# ESP32Break_Schem.net
KiCad netlist of a schematic drawn in Altium Designer
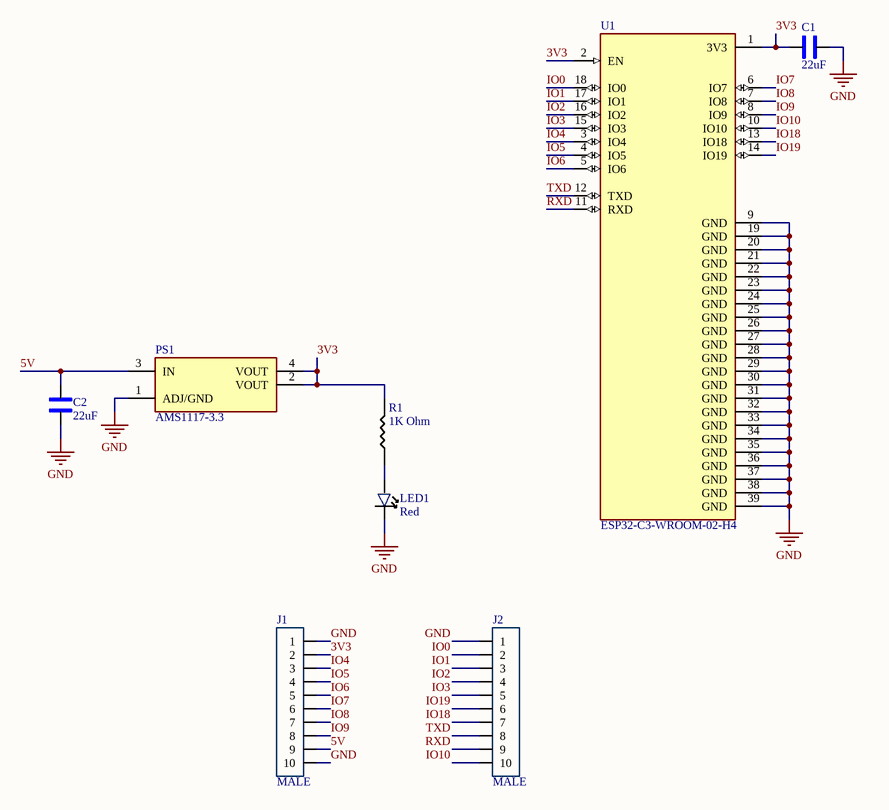
[diagram p0: ESP32Break_Schem.SchDoc]

(export (version "E")
  (design (tool "Eeschema 10.0.6"))
  (components
    (comp (ref "C1")
      (value "22uF")
      (footprint "1206_Passive_Capacitor")
      (description "22uF ±10% 25V X5R 1206 Multilayer Ceramic Capacitors MLCC - SMD/SMT RoHS")
      (fields (field (name "MFR PART #") "CL31A226KAHNNNE") (field (name "LCSC PART#") "C12891"))
      (libsource (lib "ECEN5730Lib_2023_05_DS") (part "C_22uF_1206"))
    )
    (comp (ref "C2")
      (value "22uF")
      (footprint "1206_Passive_Capacitor")
      (description "22uF ±10% 25V X5R 1206 Multilayer Ceramic Capacitors MLCC - SMD/SMT RoHS")
      (fields (field (name "MFR PART #") "CL31A226KAHNNNE") (field (name "LCSC PART#") "C12891"))
      (libsource (lib "ECEN5730Lib_2023_05_DS") (part "C_22uF_1206"))
    )
    (comp (ref "J1")
      (value "MALE")
      (footprint "10_PIN_100MIL-Male")
      (description "Pin Header 10 1 Straight ，180degrees 2.54mm Through Hole,P=2.54mm Pin Header & Female Header RoHS")
      (fields (field (name "LCSC PART#") "C124372") (field (name "Comment") "MALE 10PIN"))
      (libsource (lib "") (part "JM_10_PIN_MALE_1"))
    )
    (comp (ref "J2")
      (value "MALE")
      (footprint "10_PIN_100MIL-Male")
      (description "Pin Header 10 1 Straight ，180degrees 2.54mm Through Hole,P=2.54mm Pin Header & Female Header RoHS")
      (fields (field (name "LCSC PART#") "C124372") (field (name "Comment") "MALE 10PIN"))
      (libsource (lib "ECEN5730Lib_2023_05_DS") (part "JM_10_PIN_MALE"))
    )
    (comp (ref "LED1")
      (value "Red")
      (footprint "LED_1206")
      (description "Red 621~631nm 1206 Light Emitting Diodes (LED) RoHS")
      (fields (field (name "MFR PART #") "15-21/R6C-FQ1R1B/2T") (field (name "LCSC PART#") "C93133"))
      (libsource (lib "ECEN5730Lib_2023_05_DS") (part "LED_RED_1206"))
    )
    (comp (ref "PS1")
      (value "AMS1117-3.3")
      (footprint "LDO")
      (description "LOW DROPOUT REGULATORS(LDO) POSITIVE FIXED 1.3V @ 800MA 15V 3.3V 1A SOT-223 ROHS")
      (fields (field (name "LCSC PART#") "C6186"))
      (libsource (lib "ECEN5730Lib_2023_05_DS") (part "PS_AMS_LDO_3v3"))
    )
    (comp (ref "R1")
      (value "1K Ohm")
      (footprint "1206_Passive_Resitor")
      (description "CHIP RESISTOR - SURFACE MOUNT 1KOHMS ±1% 1/4W 1206 ROHS")
      (fields (field (name "MFR PART #") "RNCP1206FTD1K00CT") (field (name "LCSC PART#") "C4410"))
      (libsource (lib "ECEN5730Lib_2023_05_DS") (part "R_1K_1206"))
    )
    (comp (ref "U1")
      (value "ESP32-C3-WROOM-02-H4")
      (footprint "MODULE_ESP32-C3-WROOM-02-H4")
      (fields (field (name "MF") "Espressif Systems"))
      (libsource (lib "MyIntLib") (part "ESP32-C3-WROOM-02-H4"))
    )
  )
  (nets
    (net (code "1") (name "/3V3") (class "Default")
      (node (ref "C1") (pin "1") (pinfunction "1_1") (pintype "passive"))
      (node (ref "J1") (pin "2") (pinfunction "2_2") (pintype "passive"))
      (node (ref "PS1") (pin "2") (pinfunction "VOUT_2") (pintype "power_in"))
      (node (ref "PS1") (pin "4") (pinfunction "VOUT_4") (pintype "power_in"))
      (node (ref "R1") (pin "2") (pinfunction "2_2") (pintype "passive"))
      (node (ref "U1") (pin "1") (pinfunction "3V3_1") (pintype "power_in"))
      (node (ref "U1") (pin "2") (pinfunction "EN_2") (pintype "input"))
    )
    (net (code "2") (name "/5V") (class "Default")
      (node (ref "C2") (pin "1") (pinfunction "1_1") (pintype "passive"))
      (node (ref "J1") (pin "9") (pinfunction "9_9") (pintype "passive"))
      (node (ref "PS1") (pin "3") (pinfunction "IN_3") (pintype "power_in"))
    )
    (net (code "3") (name "/IO0") (class "Default")
      (node (ref "J2") (pin "2") (pinfunction "2_2") (pintype "passive"))
      (node (ref "U1") (pin "18") (pinfunction "IO0_18") (pintype "bidirectional"))
    )
    (net (code "4") (name "/IO1") (class "Default")
      (node (ref "J2") (pin "3") (pinfunction "3_3") (pintype "passive"))
      (node (ref "U1") (pin "17") (pinfunction "IO1_17") (pintype "bidirectional"))
    )
    (net (code "5") (name "/IO2") (class "Default")
      (node (ref "J2") (pin "4") (pinfunction "4_4") (pintype "passive"))
      (node (ref "U1") (pin "16") (pinfunction "IO2_16") (pintype "bidirectional"))
    )
    (net (code "6") (name "/IO3") (class "Default")
      (node (ref "J2") (pin "5") (pinfunction "5_5") (pintype "passive"))
      (node (ref "U1") (pin "15") (pinfunction "IO3_15") (pintype "bidirectional"))
    )
    (net (code "7") (name "/IO4") (class "Default")
      (node (ref "J1") (pin "3") (pinfunction "3_3") (pintype "passive"))
      (node (ref "U1") (pin "3") (pinfunction "IO4_3") (pintype "bidirectional"))
    )
    (net (code "8") (name "/IO5") (class "Default")
      (node (ref "J1") (pin "4") (pinfunction "4_4") (pintype "passive"))
      (node (ref "U1") (pin "4") (pinfunction "IO5_4") (pintype "bidirectional"))
    )
    (net (code "9") (name "/IO6") (class "Default")
      (node (ref "J1") (pin "5") (pinfunction "5_5") (pintype "passive"))
      (node (ref "U1") (pin "5") (pinfunction "IO6_5") (pintype "bidirectional"))
    )
    (net (code "10") (name "/IO7") (class "Default")
      (node (ref "J1") (pin "6") (pinfunction "6_6") (pintype "passive"))
      (node (ref "U1") (pin "6") (pinfunction "IO7_6") (pintype "bidirectional"))
    )
    (net (code "11") (name "/IO8") (class "Default")
      (node (ref "J1") (pin "7") (pinfunction "7_7") (pintype "passive"))
      (node (ref "U1") (pin "7") (pinfunction "IO8_7") (pintype "bidirectional"))
    )
    (net (code "12") (name "/IO9") (class "Default")
      (node (ref "J1") (pin "8") (pinfunction "8_8") (pintype "passive"))
      (node (ref "U1") (pin "8") (pinfunction "IO9_8") (pintype "bidirectional"))
    )
    (net (code "13") (name "/IO10") (class "Default")
      (node (ref "J2") (pin "10") (pinfunction "10_10") (pintype "passive"))
      (node (ref "U1") (pin "10") (pinfunction "IO10_10") (pintype "bidirectional"))
    )
    (net (code "14") (name "/IO18") (class "Default")
      (node (ref "J2") (pin "7") (pinfunction "7_7") (pintype "passive"))
      (node (ref "U1") (pin "13") (pinfunction "IO18_13") (pintype "bidirectional"))
    )
    (net (code "15") (name "/IO19") (class "Default")
      (node (ref "J2") (pin "6") (pinfunction "6_6") (pintype "passive"))
      (node (ref "U1") (pin "14") (pinfunction "IO19_14") (pintype "bidirectional"))
    )
    (net (code "16") (name "/RXD") (class "Default")
      (node (ref "J2") (pin "9") (pinfunction "9_9") (pintype "passive"))
      (node (ref "U1") (pin "11") (pinfunction "RXD_11") (pintype "bidirectional"))
    )
    (net (code "17") (name "/TXD") (class "Default")
      (node (ref "J2") (pin "8") (pinfunction "8_8") (pintype "passive"))
      (node (ref "U1") (pin "12") (pinfunction "TXD_12") (pintype "bidirectional"))
    )
    (net (code "18") (name "GND") (class "Default")
      (node (ref "C1") (pin "2") (pinfunction "2_2") (pintype "passive"))
      (node (ref "C2") (pin "2") (pinfunction "2_2") (pintype "passive"))
      (node (ref "J1") (pin "1") (pinfunction "1_1") (pintype "passive"))
      (node (ref "J1") (pin "10") (pinfunction "10_10") (pintype "passive"))
      (node (ref "J2") (pin "1") (pinfunction "1_1") (pintype "passive"))
      (node (ref "LED1") (pin "2") (pinfunction "2_2") (pintype "passive"))
      (node (ref "PS1") (pin "1") (pinfunction "ADJ/GND_1") (pintype "passive"))
      (node (ref "U1") (pin "19") (pinfunction "GND_19") (pintype "power_in"))
      (node (ref "U1") (pin "20") (pinfunction "GND_20") (pintype "power_in"))
      (node (ref "U1") (pin "21") (pinfunction "GND_21") (pintype "power_in"))
      (node (ref "U1") (pin "22") (pinfunction "GND_22") (pintype "power_in"))
      (node (ref "U1") (pin "23") (pinfunction "GND_23") (pintype "power_in"))
      (node (ref "U1") (pin "24") (pinfunction "GND_24") (pintype "power_in"))
      (node (ref "U1") (pin "25") (pinfunction "GND_25") (pintype "power_in"))
      (node (ref "U1") (pin "26") (pinfunction "GND_26") (pintype "power_in"))
      (node (ref "U1") (pin "27") (pinfunction "GND_27") (pintype "power_in"))
      (node (ref "U1") (pin "28") (pinfunction "GND_28") (pintype "power_in"))
      (node (ref "U1") (pin "29") (pinfunction "GND_29") (pintype "power_in"))
      (node (ref "U1") (pin "30") (pinfunction "GND_30") (pintype "power_in"))
      (node (ref "U1") (pin "31") (pinfunction "GND_31") (pintype "power_in"))
      (node (ref "U1") (pin "32") (pinfunction "GND_32") (pintype "power_in"))
      (node (ref "U1") (pin "33") (pinfunction "GND_33") (pintype "power_in"))
      (node (ref "U1") (pin "34") (pinfunction "GND_34") (pintype "power_in"))
      (node (ref "U1") (pin "35") (pinfunction "GND_35") (pintype "power_in"))
      (node (ref "U1") (pin "36") (pinfunction "GND_36") (pintype "power_in"))
      (node (ref "U1") (pin "37") (pinfunction "GND_37") (pintype "power_in"))
      (node (ref "U1") (pin "38") (pinfunction "GND_38") (pintype "power_in"))
      (node (ref "U1") (pin "39") (pinfunction "GND_39") (pintype "power_in"))
      (node (ref "U1") (pin "9") (pinfunction "GND_9") (pintype "power_in"))
    )
    (net (code "19") (name "Net-(LED1-Pad1)") (class "Default")
      (node (ref "LED1") (pin "1") (pinfunction "1_1") (pintype "passive"))
      (node (ref "R1") (pin "1") (pinfunction "1_1") (pintype "passive"))
    )
  )
)
